# sao-stripper.net
KiCad netlist of a schematic drawn in EAGLE
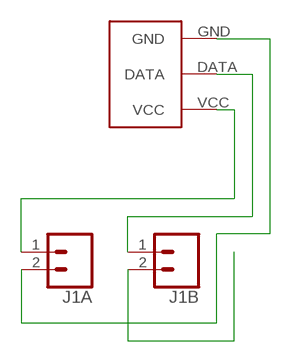
[diagram p0: schematic, sheet 1]

(export (version "E")
  (design (tool "Eeschema 10.0.6"))
  (components
    (comp (ref "J1A")
      (value "CONN_02LOCK")
      (footprint "eagle-import:1X02_LOCK")
      (libsource (lib "eagle-import") (part "CONN_02LOCK"))
    )
    (comp (ref "J1B")
      (value "CONN_02LOCK")
      (footprint "eagle-import:1X02_LOCK")
      (libsource (lib "eagle-import") (part "CONN_02LOCK"))
    )
    (comp (ref "U$1")
      (value "LEDSTRIP")
      (footprint "eagle-import:LEDSTRIP")
      (libsource (lib "eagle-import") (part "LEDSTRIP"))
    )
  )
  (nets
    (net (code "1") (name "Net-(J1A-Pad1)") (class "Default")
      (node (ref "J1A") (pin "1") (pinfunction "1_1") (pintype "passive"))
      (node (ref "U$1") (pin "VCC") (pinfunction "VCC_VCC") (pintype "bidirectional"))
    )
    (net (code "2") (name "Net-(J1A-Pad2)") (class "Default")
      (node (ref "J1A") (pin "2") (pinfunction "2_2") (pintype "passive"))
      (node (ref "U$1") (pin "GND") (pinfunction "GND_GND") (pintype "bidirectional"))
    )
    (net (code "3") (name "Net-(J1B-Pad1)") (class "Default")
      (node (ref "J1B") (pin "1") (pinfunction "1_1") (pintype "passive"))
      (node (ref "U$1") (pin "DATA") (pinfunction "DATA_DATA") (pintype "bidirectional"))
    )
    (net (code "4") (name "unconnected-(J1B-Pad2)") (class "Default")
      (node (ref "J1B") (pin "2") (pinfunction "2_2") (pintype "passive"))
    )
  )
)
